# PFC.net
KiCad netlist of a schematic drawn in Altium Designer
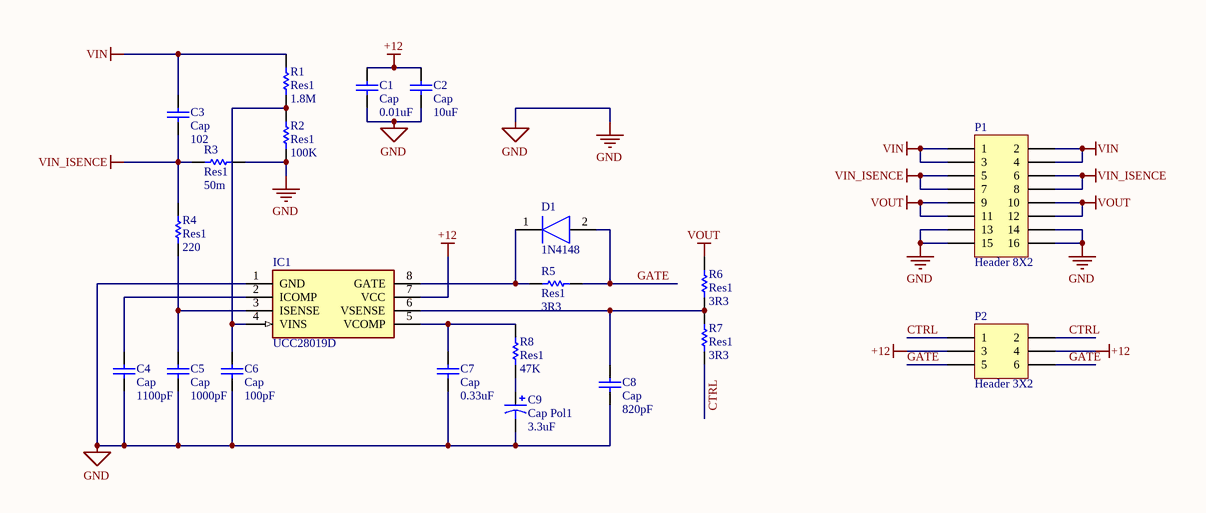
[diagram p0: PFC.SchDoc]

(export (version "E")
  (design (tool "Eeschema 10.0.6"))
  (components
    (comp (ref "C1")
      (value "Cap")
      (footprint "1608[0603]")
      (description "Capacitor")
      (fields (field (name "ALTIUM_VALUE") "0.01uF") (field (name "PUBLISHER") "Altium Limited"))
      (libsource (lib "Miscellaneous Devices") (part "Cap"))
    )
    (comp (ref "C2")
      (value "Cap")
      (footprint "1608[0603]")
      (description "Capacitor")
      (fields (field (name "ALTIUM_VALUE") "10uF") (field (name "PUBLISHER") "Altium Limited"))
      (libsource (lib "Miscellaneous Devices") (part "Cap"))
    )
    (comp (ref "C3")
      (value "Cap")
      (footprint "1608[0603]")
      (description "Capacitor")
      (fields (field (name "ALTIUM_VALUE") "102") (field (name "PUBLISHER") "Altium Limited"))
      (libsource (lib "Miscellaneous Devices") (part "Cap"))
    )
    (comp (ref "C4")
      (value "Cap")
      (footprint "1608[0603]")
      (description "Capacitor")
      (fields (field (name "ALTIUM_VALUE") "1100pF") (field (name "PUBLISHER") "Altium Limited"))
      (libsource (lib "Miscellaneous Devices") (part "Cap"))
    )
    (comp (ref "C5")
      (value "Cap")
      (footprint "1608[0603]")
      (description "Capacitor")
      (fields (field (name "ALTIUM_VALUE") "1000pF") (field (name "PUBLISHER") "Altium Limited"))
      (libsource (lib "Miscellaneous Devices") (part "Cap"))
    )
    (comp (ref "C6")
      (value "Cap")
      (footprint "1608[0603]")
      (description "Capacitor")
      (fields (field (name "ALTIUM_VALUE") "100pF") (field (name "PUBLISHER") "Altium Limited"))
      (libsource (lib "Miscellaneous Devices") (part "Cap"))
    )
    (comp (ref "C7")
      (value "Cap")
      (footprint "1608[0603]")
      (description "Capacitor")
      (fields (field (name "ALTIUM_VALUE") "0.33uF") (field (name "PUBLISHER") "Altium Limited"))
      (libsource (lib "Miscellaneous Devices") (part "Cap"))
    )
    (comp (ref "C8")
      (value "Cap")
      (footprint "1608[0603]")
      (description "Capacitor")
      (fields (field (name "ALTIUM_VALUE") "820pF") (field (name "PUBLISHER") "Altium Limited"))
      (libsource (lib "Miscellaneous Devices") (part "Cap"))
    )
    (comp (ref "C9")
      (value "Cap Pol1")
      (footprint "1608[0603]")
      (description "Polarized Capacitor (Radial)")
      (fields (field (name "ALTIUM_VALUE") "3.3uF") (field (name "PUBLISHER") "Altium Limited"))
      (libsource (lib "Miscellaneous Devices") (part "Cap Pol1"))
    )
    (comp (ref "D1")
      (value "1N4148")
      (footprint "SamacSys:DIOAD1068W53L380D172")
      (description "Diode")
      (fields (field (name "MOUSER PART NUMBER") "833-1N4148"))
      (libsource (lib "*") (part "1N4148"))
    )
    (comp (ref "IC1")
      (value "UCC28019D")
      (footprint "SamacSys:SOIC127P600X175-8N")
      (description "Integrated Circuit")
      (fields (field (name "RS PART NUMBER") "0404342P"))
      (libsource (lib "*") (part "UCC28019D"))
    )
    (comp (ref "P1")
      (value "Header 8X2")
      (footprint "HDR2X8")
      (description "Header, 8-Pin, Dual row")
      (fields (field (name "PUBLISHER") "Altium Limited"))
      (libsource (lib "Miscellaneous Connectors") (part "Header 8X2"))
    )
    (comp (ref "P2")
      (value "Header 3X2")
      (footprint "HDR2X3")
      (description "Header, 3-Pin, Dual row")
      (fields (field (name "PUBLISHER") "Altium Limited"))
      (libsource (lib "Miscellaneous Connectors") (part "Header 3X2"))
    )
    (comp (ref "R1")
      (value "Res1")
      (footprint "1608[0603]")
      (description "Resistor")
      (fields (field (name "ALTIUM_VALUE") "1.8M") (field (name "PUBLISHER") "Altium Limited"))
      (libsource (lib "Miscellaneous Devices") (part "Res1"))
    )
    (comp (ref "R2")
      (value "Res1")
      (footprint "1608[0603]")
      (description "Resistor")
      (fields (field (name "ALTIUM_VALUE") "100K") (field (name "PUBLISHER") "Altium Limited"))
      (libsource (lib "Miscellaneous Devices") (part "Res1"))
    )
    (comp (ref "R3")
      (value "Res1")
      (footprint "C1210")
      (description "Resistor")
      (fields (field (name "ALTIUM_VALUE") "50m") (field (name "PUBLISHER") "Altium Limited"))
      (libsource (lib "Miscellaneous Devices") (part "Res1"))
    )
    (comp (ref "R4")
      (value "Res1")
      (footprint "1608[0603]")
      (description "Resistor")
      (fields (field (name "ALTIUM_VALUE") "220") (field (name "PUBLISHER") "Altium Limited"))
      (libsource (lib "Miscellaneous Devices") (part "Res1"))
    )
    (comp (ref "R5")
      (value "Res1")
      (footprint "1608[0603]")
      (description "Resistor")
      (fields (field (name "ALTIUM_VALUE") "3R3") (field (name "PUBLISHER") "Altium Limited"))
      (libsource (lib "Miscellaneous Devices") (part "Res1"))
    )
    (comp (ref "R6")
      (value "Res1")
      (footprint "1608[0603]")
      (description "Resistor")
      (fields (field (name "ALTIUM_VALUE") "3R3") (field (name "PUBLISHER") "Altium Limited"))
      (libsource (lib "Miscellaneous Devices") (part "Res1"))
    )
    (comp (ref "R7")
      (value "Res1")
      (footprint "1608[0603]")
      (description "Resistor")
      (fields (field (name "ALTIUM_VALUE") "3R3") (field (name "PUBLISHER") "Altium Limited"))
      (libsource (lib "Miscellaneous Devices") (part "Res1"))
    )
    (comp (ref "R8")
      (value "Res1")
      (footprint "1608[0603]")
      (description "Resistor")
      (fields (field (name "ALTIUM_VALUE") "47K") (field (name "PUBLISHER") "Altium Limited"))
      (libsource (lib "Miscellaneous Devices") (part "Res1"))
    )
  )
  (nets
    (net (code "1") (name "+12") (class "Default")
      (node (ref "C1") (pin "2") (pinfunction "2_2") (pintype "passive"))
      (node (ref "C2") (pin "2") (pinfunction "2_2") (pintype "passive"))
      (node (ref "IC1") (pin "7") (pinfunction "VCC_7") (pintype "power_in"))
      (node (ref "P2") (pin "3") (pinfunction "3_3") (pintype "passive"))
      (node (ref "P2") (pin "4") (pinfunction "4_4") (pintype "passive"))
    )
    (net (code "2") (name "/CTRL") (class "Default")
      (node (ref "P2") (pin "1") (pinfunction "1_1") (pintype "passive"))
      (node (ref "P2") (pin "2") (pinfunction "2_2") (pintype "passive"))
      (node (ref "R7") (pin "1") (pinfunction "1_1") (pintype "passive"))
    )
    (net (code "3") (name "/GATE") (class "Default")
      (node (ref "D1") (pin "2") (pinfunction "A_2") (pintype "passive"))
      (node (ref "P2") (pin "5") (pinfunction "5_5") (pintype "passive"))
      (node (ref "P2") (pin "6") (pinfunction "6_6") (pintype "passive"))
      (node (ref "R5") (pin "2") (pinfunction "2_2") (pintype "passive"))
    )
    (net (code "4") (name "GND") (class "Default")
      (node (ref "C1") (pin "1") (pinfunction "1_1") (pintype "passive"))
      (node (ref "C2") (pin "1") (pinfunction "1_1") (pintype "passive"))
      (node (ref "C4") (pin "1") (pinfunction "1_1") (pintype "passive"))
      (node (ref "C5") (pin "1") (pinfunction "1_1") (pintype "passive"))
      (node (ref "C6") (pin "1") (pinfunction "1_1") (pintype "passive"))
      (node (ref "C7") (pin "1") (pinfunction "1_1") (pintype "passive"))
      (node (ref "C8") (pin "1") (pinfunction "1_1") (pintype "passive"))
      (node (ref "C9") (pin "2") (pinfunction "2_2") (pintype "passive"))
      (node (ref "IC1") (pin "1") (pinfunction "GND_1") (pintype "power_in"))
      (node (ref "P1") (pin "13") (pinfunction "13_13") (pintype "passive"))
      (node (ref "P1") (pin "14") (pinfunction "14_14") (pintype "passive"))
      (node (ref "P1") (pin "15") (pinfunction "15_15") (pintype "passive"))
      (node (ref "P1") (pin "16") (pinfunction "16_16") (pintype "passive"))
      (node (ref "R2") (pin "2") (pinfunction "2_2") (pintype "passive"))
      (node (ref "R3") (pin "1") (pinfunction "1_1") (pintype "passive"))
    )
    (net (code "5") (name "Net-(C9-Pad1)") (class "Default")
      (node (ref "C9") (pin "1") (pinfunction "1_1") (pintype "passive"))
      (node (ref "R8") (pin "1") (pinfunction "1_1") (pintype "passive"))
    )
    (net (code "6") (name "Net-(D1-K)") (class "Default")
      (node (ref "D1") (pin "1") (pinfunction "K_1") (pintype "passive"))
      (node (ref "IC1") (pin "8") (pinfunction "GATE_8") (pintype "passive"))
      (node (ref "R5") (pin "1") (pinfunction "1_1") (pintype "passive"))
    )
    (net (code "7") (name "Net-(IC1-ICOMP)") (class "Default")
      (node (ref "C4") (pin "2") (pinfunction "2_2") (pintype "passive"))
      (node (ref "IC1") (pin "2") (pinfunction "ICOMP_2") (pintype "passive"))
    )
    (net (code "8") (name "Net-(IC1-ISENSE)") (class "Default")
      (node (ref "C5") (pin "2") (pinfunction "2_2") (pintype "passive"))
      (node (ref "IC1") (pin "3") (pinfunction "ISENSE_3") (pintype "passive"))
      (node (ref "R4") (pin "1") (pinfunction "1_1") (pintype "passive"))
    )
    (net (code "9") (name "Net-(IC1-VCOMP)") (class "Default")
      (node (ref "C7") (pin "2") (pinfunction "2_2") (pintype "passive"))
      (node (ref "IC1") (pin "5") (pinfunction "VCOMP_5") (pintype "passive"))
      (node (ref "R8") (pin "2") (pinfunction "2_2") (pintype "passive"))
    )
    (net (code "10") (name "Net-(IC1-VINS)") (class "Default")
      (node (ref "C6") (pin "2") (pinfunction "2_2") (pintype "passive"))
      (node (ref "IC1") (pin "4") (pinfunction "VINS_4") (pintype "input"))
      (node (ref "R1") (pin "2") (pinfunction "2_2") (pintype "passive"))
      (node (ref "R2") (pin "1") (pinfunction "1_1") (pintype "passive"))
    )
    (net (code "11") (name "Net-(IC1-VSENSE)") (class "Default")
      (node (ref "C8") (pin "2") (pinfunction "2_2") (pintype "passive"))
      (node (ref "IC1") (pin "6") (pinfunction "VSENSE_6") (pintype "passive"))
      (node (ref "R6") (pin "1") (pinfunction "1_1") (pintype "passive"))
      (node (ref "R7") (pin "2") (pinfunction "2_2") (pintype "passive"))
    )
    (net (code "12") (name "VIN") (class "Default")
      (node (ref "C3") (pin "2") (pinfunction "2_2") (pintype "passive"))
      (node (ref "P1") (pin "1") (pinfunction "1_1") (pintype "passive"))
      (node (ref "P1") (pin "2") (pinfunction "2_2") (pintype "passive"))
      (node (ref "P1") (pin "3") (pinfunction "3_3") (pintype "passive"))
      (node (ref "P1") (pin "4") (pinfunction "4_4") (pintype "passive"))
      (node (ref "R1") (pin "1") (pinfunction "1_1") (pintype "passive"))
    )
    (net (code "13") (name "VIN_ISENCE") (class "Default")
      (node (ref "C3") (pin "1") (pinfunction "1_1") (pintype "passive"))
      (node (ref "P1") (pin "5") (pinfunction "5_5") (pintype "passive"))
      (node (ref "P1") (pin "6") (pinfunction "6_6") (pintype "passive"))
      (node (ref "P1") (pin "7") (pinfunction "7_7") (pintype "passive"))
      (node (ref "P1") (pin "8") (pinfunction "8_8") (pintype "passive"))
      (node (ref "R3") (pin "2") (pinfunction "2_2") (pintype "passive"))
      (node (ref "R4") (pin "2") (pinfunction "2_2") (pintype "passive"))
    )
    (net (code "14") (name "VOUT") (class "Default")
      (node (ref "P1") (pin "10") (pinfunction "10_10") (pintype "passive"))
      (node (ref "P1") (pin "11") (pinfunction "11_11") (pintype "passive"))
      (node (ref "P1") (pin "12") (pinfunction "12_12") (pintype "passive"))
      (node (ref "P1") (pin "9") (pinfunction "9_9") (pintype "passive"))
      (node (ref "R6") (pin "2") (pinfunction "2_2") (pintype "passive"))
    )
  )
)
